# TP4059.net
KiCad netlist of a schematic drawn in Altium Designer
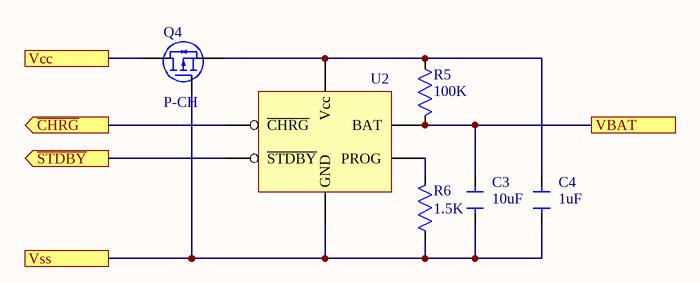
[diagram p0: TP4059.SchDoc]

(export (version "E")
  (design (tool "Eeschema 10.0.6"))
  (components
    (comp (ref "C3")
      (value "10uF")
      (footprint "Cap_0603")
      (fields (field (name "Comment") "Cap"))
      (libsource (lib "ZGR") (part "Cap"))
    )
    (comp (ref "C4")
      (value "1uF")
      (footprint "Cap_0603")
      (fields (field (name "Comment") "Cap"))
      (libsource (lib "ZGR") (part "Cap"))
    )
    (comp (ref "Q4")
      (value "SI2301DS-T1")
      (footprint "SOT-23")
      (description "Trans MOSFET P-CH 20V 2.3A 3-Pin TO-236 T/R")
      (fields (field (name "MANUFACTURER") "Vishay Siliconix") (field (name "POLARITY") "P-CH"))
      (libsource (lib "ZGR") (part "SI2301DS-T1"))
    )
    (comp (ref "R5")
      (value "100K")
      (footprint "RES_0402")
      (fields (field (name "Comment") "Res"))
      (libsource (lib "ZGR") (part "Res"))
    )
    (comp (ref "R6")
      (value "1.5K")
      (footprint "RES_0402")
      (fields (field (name "Comment") "Res"))
      (libsource (lib "ZGR") (part "Res"))
    )
    (comp (ref "U2")
      (value "TP4059")
      (footprint "SOT23-6")
      (description "600MA SOT23-6")
      (libsource (lib "ZGR") (part "TP4059"))
    )
  )
  (nets
    (net (code "1") (name "/CHRG") (class "Default")
      (node (ref "U2") (pin "2") (pinfunction "CHRG_2") (pintype "passive"))
    )
    (net (code "2") (name "/STDBY") (class "Default")
      (node (ref "U2") (pin "3") (pinfunction "STDBY_3") (pintype "open_collector"))
    )
    (net (code "3") (name "/VBAT") (class "Default")
      (node (ref "C3") (pin "1") (pinfunction "1_1") (pintype "passive"))
      (node (ref "R5") (pin "1") (pinfunction "1_1") (pintype "passive"))
      (node (ref "U2") (pin "6") (pinfunction "BAT_6") (pintype "power_in"))
    )
    (net (code "4") (name "/Vcc") (class "Default")
      (node (ref "Q4") (pin "1") (pinfunction "1_1") (pintype "passive"))
    )
    (net (code "5") (name "/Vss") (class "Default")
      (node (ref "C3") (pin "2") (pinfunction "2_2") (pintype "passive"))
      (node (ref "C4") (pin "2") (pinfunction "2_2") (pintype "passive"))
      (node (ref "Q4") (pin "2") (pinfunction "2_2") (pintype "passive"))
      (node (ref "R6") (pin "2") (pinfunction "2_2") (pintype "passive"))
      (node (ref "U2") (pin "4") (pinfunction "GND_4") (pintype "power_in"))
    )
    (net (code "6") (name "Net-(U2-PROG)") (class "Default")
      (node (ref "R6") (pin "1") (pinfunction "1_1") (pintype "passive"))
      (node (ref "U2") (pin "5") (pinfunction "PROG_5") (pintype "passive"))
    )
    (net (code "7") (name "Net-(U2-Vcc)") (class "Default")
      (node (ref "C4") (pin "1") (pinfunction "1_1") (pintype "passive"))
      (node (ref "Q4") (pin "3") (pinfunction "3_3") (pintype "passive"))
      (node (ref "R5") (pin "2") (pinfunction "2_2") (pintype "passive"))
      (node (ref "U2") (pin "1") (pinfunction "Vcc_1") (pintype "power_in"))
    )
  )
)
